# Mpr121Shield.net
KiCad netlist of a schematic drawn in EAGLE
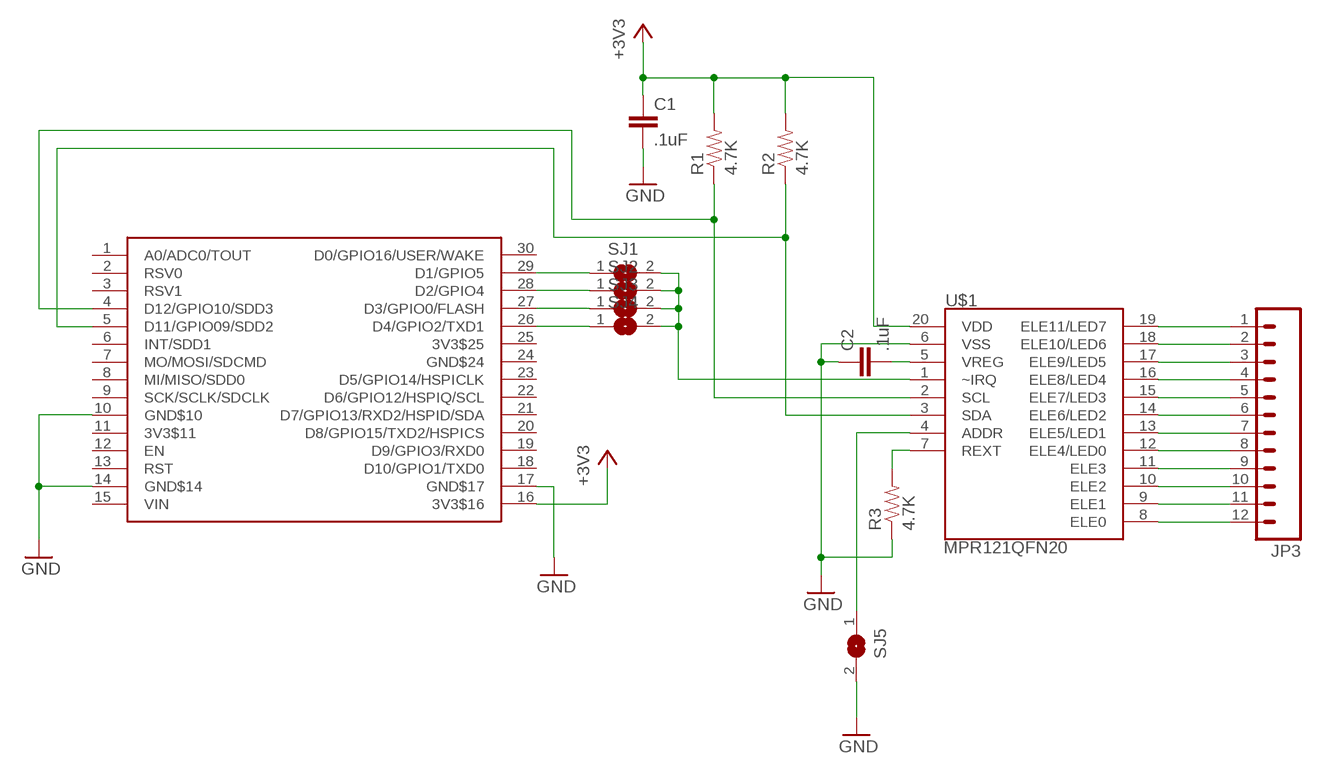
[diagram p0: schematic, sheet 1]

(export (version "E")
  (design (tool "Eeschema 10.0.6"))
  (components
    (comp (ref "C1")
      (value ".1uF")
      (footprint "eagle-import:0603-CAP")
      (libsource (lib "eagle-import") (part "CAP0603-CAP"))
    )
    (comp (ref "C2")
      (value ".1uF")
      (footprint "eagle-import:0603-CAP")
      (libsource (lib "eagle-import") (part "CAP0603-CAP"))
    )
    (comp (ref "JP3")
      (value "M12NO_SILK")
      (footprint "eagle-import:1X12_NO_SILK")
      (libsource (lib "eagle-import") (part "M12NO_SILK"))
    )
    (comp (ref "R1")
      (value "4.7K")
      (footprint "eagle-import:0603-RES")
      (libsource (lib "eagle-import") (part "RESISTOR0603-RES"))
    )
    (comp (ref "R2")
      (value "4.7K")
      (footprint "eagle-import:0603-RES")
      (libsource (lib "eagle-import") (part "RESISTOR0603-RES"))
    )
    (comp (ref "R3")
      (value "4.7K")
      (footprint "eagle-import:0603-RES")
      (libsource (lib "eagle-import") (part "RESISTOR0603-RES"))
    )
    (comp (ref "SJ1") (value "SJ") (footprint "eagle-import:SJ") (libsource (lib "eagle-import") (part "SJ")))
    (comp (ref "SJ2") (value "SJ") (footprint "eagle-import:SJ") (libsource (lib "eagle-import") (part "SJ")))
    (comp (ref "SJ3") (value "SJ") (footprint "eagle-import:SJ") (libsource (lib "eagle-import") (part "SJ")))
    (comp (ref "SJ4") (value "SJ") (footprint "eagle-import:SJ") (libsource (lib "eagle-import") (part "SJ")))
    (comp (ref "SJ5") (value "SJ") (footprint "eagle-import:SJ") (libsource (lib "eagle-import") (part "SJ")))
    (comp (ref "U$1")
      (value "MPR121QFN20")
      (footprint "eagle-import:QFN-20-0.4MM")
      (libsource (lib "eagle-import") (part "MPR121QFN20"))
    )
    (comp (ref "U$2")
      (value "NERDSHIELD")
      (footprint "eagle-import:NERDUINO_STACK")
      (libsource (lib "eagle-import") (part "NERDSHIELD"))
    )
  )
  (nets
    (net (code "1") (name "+3V3") (class "Default")
      (node (ref "C1") (pin "1") (pinfunction "1_1") (pintype "passive"))
      (node (ref "R1") (pin "2") (pinfunction "2_2") (pintype "passive"))
      (node (ref "R2") (pin "2") (pinfunction "2_2") (pintype "passive"))
      (node (ref "U$1") (pin "20") (pinfunction "VDD_20") (pintype "bidirectional"))
      (node (ref "U$2") (pin "16") (pinfunction "3V3$16_16") (pintype "bidirectional"))
    )
    (net (code "2") (name "GND") (class "Default")
      (node (ref "C1") (pin "2") (pinfunction "2_2") (pintype "passive"))
      (node (ref "C2") (pin "1") (pinfunction "1_1") (pintype "passive"))
      (node (ref "R3") (pin "1") (pinfunction "1_1") (pintype "passive"))
      (node (ref "SJ5") (pin "2") (pinfunction "2_2") (pintype "passive"))
      (node (ref "U$1") (pin "6") (pinfunction "VSS_6") (pintype "bidirectional"))
      (node (ref "U$2") (pin "10") (pinfunction "GND$10_10") (pintype "bidirectional"))
      (node (ref "U$2") (pin "14") (pinfunction "GND$14_14") (pintype "bidirectional"))
      (node (ref "U$2") (pin "17") (pinfunction "GND$17_17") (pintype "bidirectional"))
    )
    (net (code "3") (name "Net-(U$1-ADDR)") (class "Default")
      (node (ref "SJ5") (pin "1") (pinfunction "1_1") (pintype "passive"))
      (node (ref "U$1") (pin "4") (pinfunction "ADDR_4") (pintype "bidirectional"))
    )
    (net (code "4") (name "Net-(U$1-ELE0)") (class "Default")
      (node (ref "JP3") (pin "12") (pinfunction "12_12") (pintype "passive"))
      (node (ref "U$1") (pin "8") (pinfunction "ELE0_8") (pintype "bidirectional"))
    )
    (net (code "5") (name "Net-(U$1-ELE1)") (class "Default")
      (node (ref "JP3") (pin "11") (pinfunction "11_11") (pintype "passive"))
      (node (ref "U$1") (pin "9") (pinfunction "ELE1_9") (pintype "bidirectional"))
    )
    (net (code "6") (name "Net-(U$1-ELE2)") (class "Default")
      (node (ref "JP3") (pin "10") (pinfunction "10_10") (pintype "passive"))
      (node (ref "U$1") (pin "10") (pinfunction "ELE2_10") (pintype "bidirectional"))
    )
    (net (code "7") (name "Net-(U$1-ELE3)") (class "Default")
      (node (ref "JP3") (pin "9") (pinfunction "9_9") (pintype "passive"))
      (node (ref "U$1") (pin "11") (pinfunction "ELE3_11") (pintype "bidirectional"))
    )
    (net (code "8") (name "Net-(U$1-ELE4{slash}LED0)") (class "Default")
      (node (ref "JP3") (pin "8") (pinfunction "8_8") (pintype "passive"))
      (node (ref "U$1") (pin "12") (pinfunction "ELE4/LED0_12") (pintype "bidirectional"))
    )
    (net (code "9") (name "Net-(U$1-ELE5{slash}LED1)") (class "Default")
      (node (ref "JP3") (pin "7") (pinfunction "7_7") (pintype "passive"))
      (node (ref "U$1") (pin "13") (pinfunction "ELE5/LED1_13") (pintype "bidirectional"))
    )
    (net (code "10") (name "Net-(U$1-ELE6{slash}LED2)") (class "Default")
      (node (ref "JP3") (pin "6") (pinfunction "6_6") (pintype "passive"))
      (node (ref "U$1") (pin "14") (pinfunction "ELE6/LED2_14") (pintype "bidirectional"))
    )
    (net (code "11") (name "Net-(U$1-ELE7{slash}LED3)") (class "Default")
      (node (ref "JP3") (pin "5") (pinfunction "5_5") (pintype "passive"))
      (node (ref "U$1") (pin "15") (pinfunction "ELE7/LED3_15") (pintype "bidirectional"))
    )
    (net (code "12") (name "Net-(U$1-ELE8{slash}LED4)") (class "Default")
      (node (ref "JP3") (pin "4") (pinfunction "4_4") (pintype "passive"))
      (node (ref "U$1") (pin "16") (pinfunction "ELE8/LED4_16") (pintype "bidirectional"))
    )
    (net (code "13") (name "Net-(U$1-ELE9{slash}LED5)") (class "Default")
      (node (ref "JP3") (pin "3") (pinfunction "3_3") (pintype "passive"))
      (node (ref "U$1") (pin "17") (pinfunction "ELE9/LED5_17") (pintype "bidirectional"))
    )
    (net (code "14") (name "Net-(U$1-ELE10{slash}LED6)") (class "Default")
      (node (ref "JP3") (pin "2") (pinfunction "2_2") (pintype "passive"))
      (node (ref "U$1") (pin "18") (pinfunction "ELE10/LED6_18") (pintype "bidirectional"))
    )
    (net (code "15") (name "Net-(U$1-ELE11{slash}LED7)") (class "Default")
      (node (ref "JP3") (pin "1") (pinfunction "1_1") (pintype "passive"))
      (node (ref "U$1") (pin "19") (pinfunction "ELE11/LED7_19") (pintype "bidirectional"))
    )
    (net (code "16") (name "Net-(U$1-REXT)") (class "Default")
      (node (ref "R3") (pin "2") (pinfunction "2_2") (pintype "passive"))
      (node (ref "U$1") (pin "7") (pinfunction "REXT_7") (pintype "bidirectional"))
    )
    (net (code "17") (name "Net-(U$1-SCL)") (class "Default")
      (node (ref "R1") (pin "1") (pinfunction "1_1") (pintype "passive"))
      (node (ref "U$1") (pin "2") (pinfunction "SCL_2") (pintype "bidirectional"))
      (node (ref "U$2") (pin "4") (pinfunction "D12/GPIO10/SDD3_4") (pintype "bidirectional"))
    )
    (net (code "18") (name "Net-(U$1-SDA)") (class "Default")
      (node (ref "R2") (pin "1") (pinfunction "1_1") (pintype "passive"))
      (node (ref "U$1") (pin "3") (pinfunction "SDA_3") (pintype "bidirectional"))
      (node (ref "U$2") (pin "5") (pinfunction "D11/GPIO09/SDD2_5") (pintype "bidirectional"))
    )
    (net (code "19") (name "Net-(U$1-VREG)") (class "Default")
      (node (ref "C2") (pin "2") (pinfunction "2_2") (pintype "passive"))
      (node (ref "U$1") (pin "5") (pinfunction "VREG_5") (pintype "bidirectional"))
    )
    (net (code "20") (name "Net-(U$1-~{IRQ})") (class "Default")
      (node (ref "SJ1") (pin "2") (pinfunction "2_2") (pintype "passive"))
      (node (ref "SJ2") (pin "2") (pinfunction "2_2") (pintype "passive"))
      (node (ref "SJ3") (pin "2") (pinfunction "2_2") (pintype "passive"))
      (node (ref "SJ4") (pin "2") (pinfunction "2_2") (pintype "passive"))
      (node (ref "U$1") (pin "1") (pinfunction "~{IRQ}_1") (pintype "bidirectional"))
    )
    (net (code "21") (name "Net-(U$2-D1{slash}GPIO5)") (class "Default")
      (node (ref "SJ1") (pin "1") (pinfunction "1_1") (pintype "passive"))
      (node (ref "U$2") (pin "29") (pinfunction "D1/GPIO5_29") (pintype "bidirectional"))
    )
    (net (code "22") (name "Net-(U$2-D2{slash}GPIO4)") (class "Default")
      (node (ref "SJ2") (pin "1") (pinfunction "1_1") (pintype "passive"))
      (node (ref "U$2") (pin "28") (pinfunction "D2/GPIO4_28") (pintype "bidirectional"))
    )
    (net (code "23") (name "Net-(U$2-D3{slash}GPIO0{slash}FLASH)") (class "Default")
      (node (ref "SJ3") (pin "1") (pinfunction "1_1") (pintype "passive"))
      (node (ref "U$2") (pin "27") (pinfunction "D3/GPIO0/FLASH_27") (pintype "bidirectional"))
    )
    (net (code "24") (name "Net-(U$2-D4{slash}GPIO2{slash}TXD1)") (class "Default")
      (node (ref "SJ4") (pin "1") (pinfunction "1_1") (pintype "passive"))
      (node (ref "U$2") (pin "26") (pinfunction "D4/GPIO2/TXD1_26") (pintype "bidirectional"))
    )
    (net (code "25") (name "unconnected-(U$2-3V3$11-Pad11)") (class "Default")
      (node (ref "U$2") (pin "11") (pinfunction "3V3$11_11") (pintype "bidirectional"))
    )
    (net (code "26") (name "unconnected-(U$2-3V3$25-Pad25)") (class "Default")
      (node (ref "U$2") (pin "25") (pinfunction "3V3$25_25") (pintype "bidirectional"))
    )
    (net (code "27") (name "unconnected-(U$2-A0{slash}ADC0{slash}TOUT-Pad1)") (class "Default")
      (node (ref "U$2") (pin "1") (pinfunction "A0/ADC0/TOUT_1") (pintype "bidirectional"))
    )
    (net (code "28") (name "unconnected-(U$2-D0{slash}GPIO16{slash}USER{slash}WAKE-Pad30)") (class "Default")
      (node (ref "U$2") (pin "30") (pinfunction "D0/GPIO16/USER/WAKE_30") (pintype "bidirectional"))
    )
    (net (code "29") (name "unconnected-(U$2-D5{slash}GPIO14{slash}HSPICLK-Pad23)") (class "Default")
      (node (ref "U$2") (pin "23") (pinfunction "D5/GPIO14/HSPICLK_23") (pintype "bidirectional"))
    )
    (net (code "30") (name "unconnected-(U$2-D6{slash}GPIO12{slash}HSPIQ{slash}SCL-Pad22)") (class "Default")
      (node (ref "U$2") (pin "22") (pinfunction "D6/GPIO12/HSPIQ/SCL_22") (pintype "bidirectional"))
    )
    (net (code "31") (name "unconnected-(U$2-D7{slash}GPIO13{slash}RXD2{slash}HSPID{slash}SDA-Pad21)") (class "Default")
      (node (ref "U$2") (pin "21") (pinfunction "D7/GPIO13/RXD2/HSPID/SDA_21") (pintype "bidirectional"))
    )
    (net (code "32") (name "unconnected-(U$2-D8{slash}GPIO15{slash}TXD2{slash}HSPICS-Pad20)") (class "Default")
      (node (ref "U$2") (pin "20") (pinfunction "D8/GPIO15/TXD2/HSPICS_20") (pintype "bidirectional"))
    )
    (net (code "33") (name "unconnected-(U$2-D9{slash}GPIO3{slash}RXD0-Pad19)") (class "Default")
      (node (ref "U$2") (pin "19") (pinfunction "D9/GPIO3/RXD0_19") (pintype "bidirectional"))
    )
    (net (code "34") (name "unconnected-(U$2-D10{slash}GPIO1{slash}TXD0-Pad18)") (class "Default")
      (node (ref "U$2") (pin "18") (pinfunction "D10/GPIO1/TXD0_18") (pintype "bidirectional"))
    )
    (net (code "35") (name "unconnected-(U$2-EN-Pad12)") (class "Default")
      (node (ref "U$2") (pin "12") (pinfunction "EN_12") (pintype "bidirectional"))
    )
    (net (code "36") (name "unconnected-(U$2-GND$24-Pad24)") (class "Default")
      (node (ref "U$2") (pin "24") (pinfunction "GND$24_24") (pintype "bidirectional"))
    )
    (net (code "37") (name "unconnected-(U$2-INT{slash}SDD1-Pad6)") (class "Default")
      (node (ref "U$2") (pin "6") (pinfunction "INT/SDD1_6") (pintype "bidirectional"))
    )
    (net (code "38") (name "unconnected-(U$2-MI{slash}MISO{slash}SDD0-Pad8)") (class "Default")
      (node (ref "U$2") (pin "8") (pinfunction "MI/MISO/SDD0_8") (pintype "bidirectional"))
    )
    (net (code "39") (name "unconnected-(U$2-MO{slash}MOSI{slash}SDCMD-Pad7)") (class "Default")
      (node (ref "U$2") (pin "7") (pinfunction "MO/MOSI/SDCMD_7") (pintype "bidirectional"))
    )
    (net (code "40") (name "unconnected-(U$2-RST-Pad13)") (class "Default")
      (node (ref "U$2") (pin "13") (pinfunction "RST_13") (pintype "bidirectional"))
    )
    (net (code "41") (name "unconnected-(U$2-RSV0-Pad2)") (class "Default")
      (node (ref "U$2") (pin "2") (pinfunction "RSV0_2") (pintype "bidirectional"))
    )
    (net (code "42") (name "unconnected-(U$2-RSV1-Pad3)") (class "Default")
      (node (ref "U$2") (pin "3") (pinfunction "RSV1_3") (pintype "bidirectional"))
    )
    (net (code "43") (name "unconnected-(U$2-SCK{slash}SCLK{slash}SDCLK-Pad9)") (class "Default")
      (node (ref "U$2") (pin "9") (pinfunction "SCK/SCLK/SDCLK_9") (pintype "bidirectional"))
    )
    (net (code "44") (name "unconnected-(U$2-VIN-Pad15)") (class "Default")
      (node (ref "U$2") (pin "15") (pinfunction "VIN_15") (pintype "bidirectional"))
    )
  )
)
